# pi_zero_drone_controller_hat.net
KiCad netlist of a schematic drawn in EAGLE
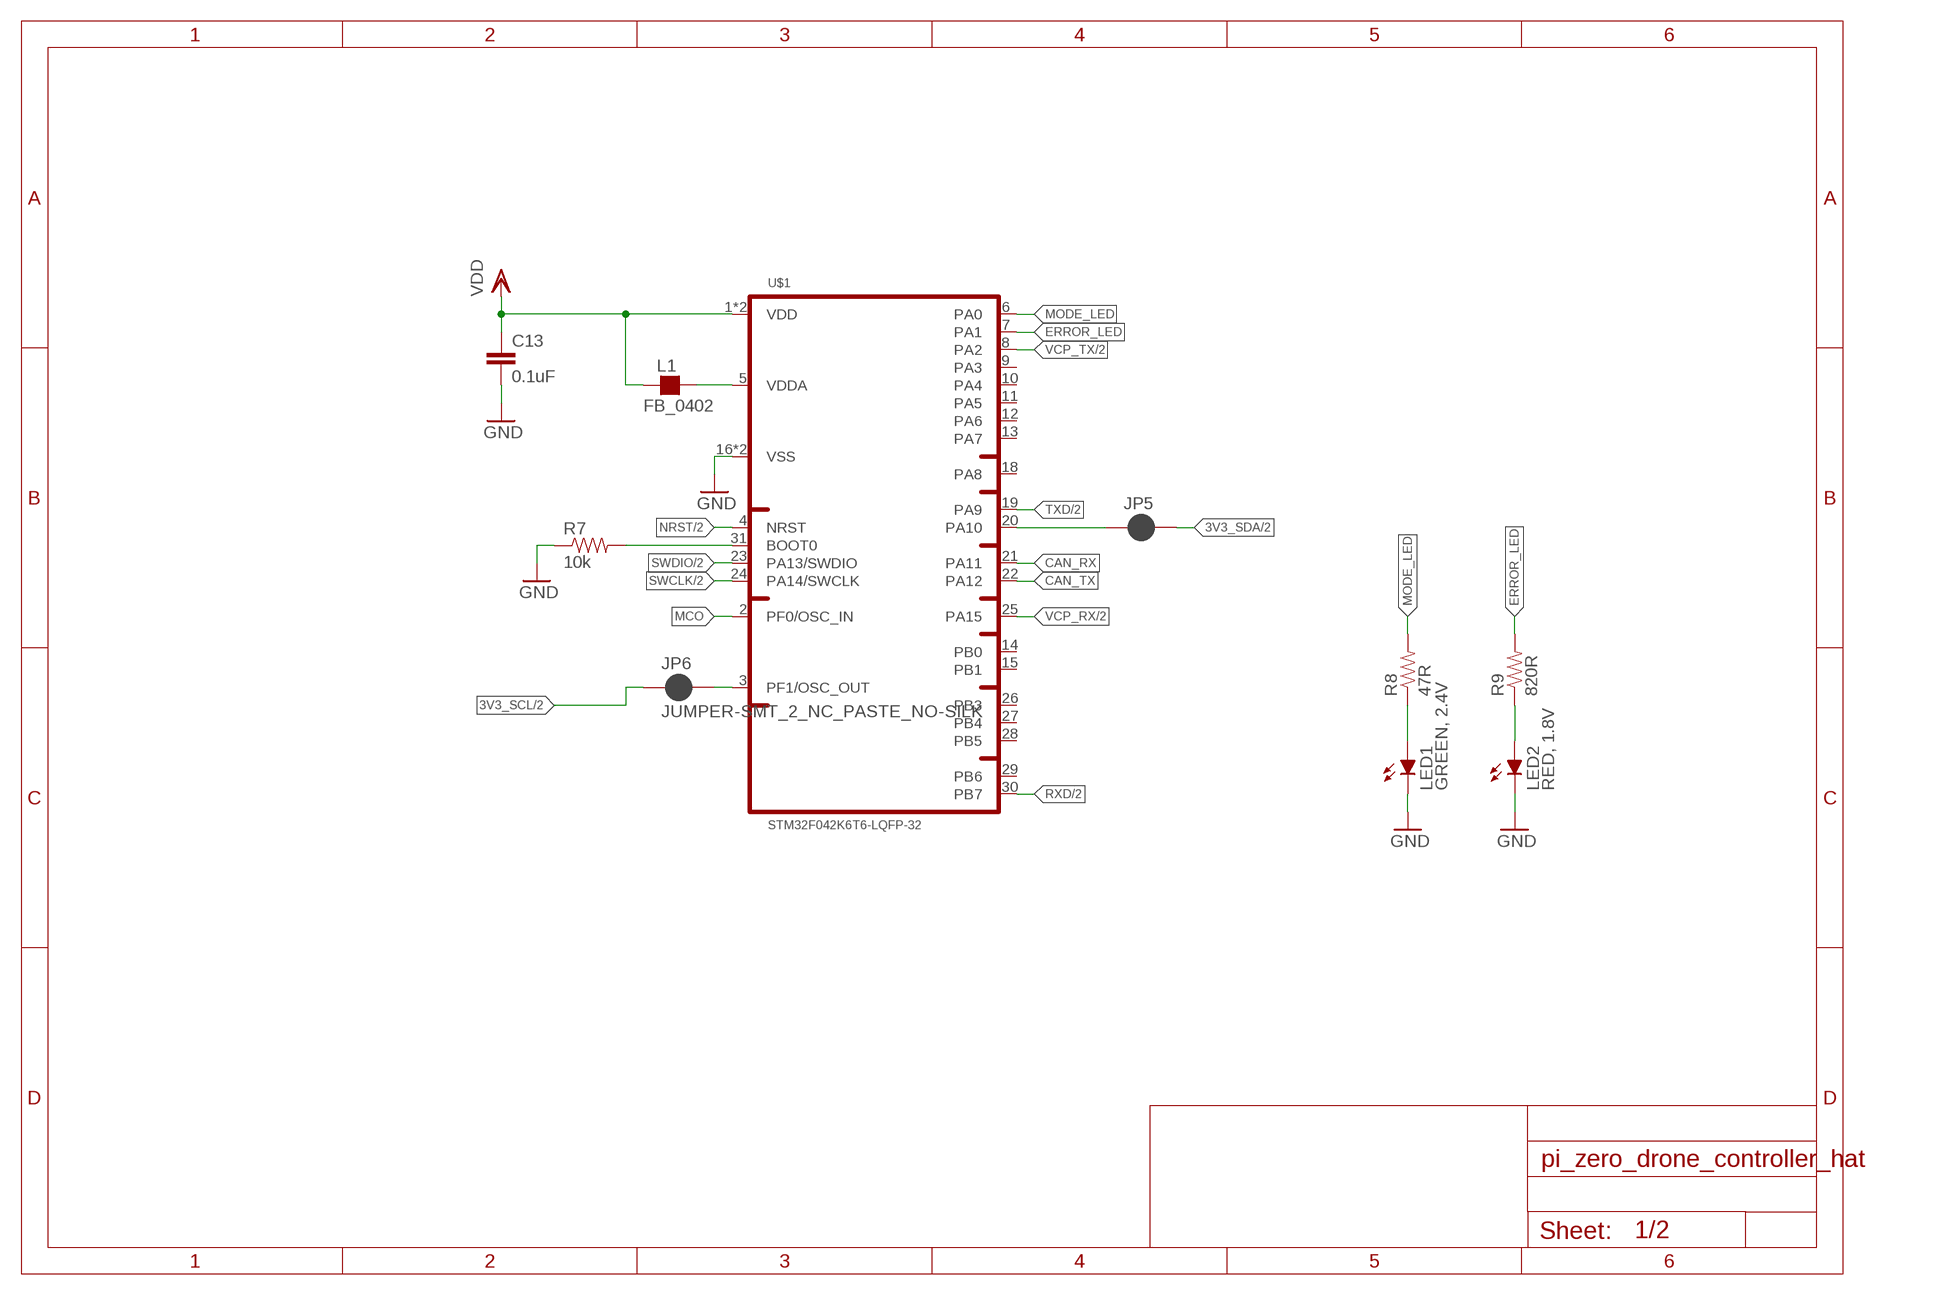
[diagram p0: schematic, sheet 1]
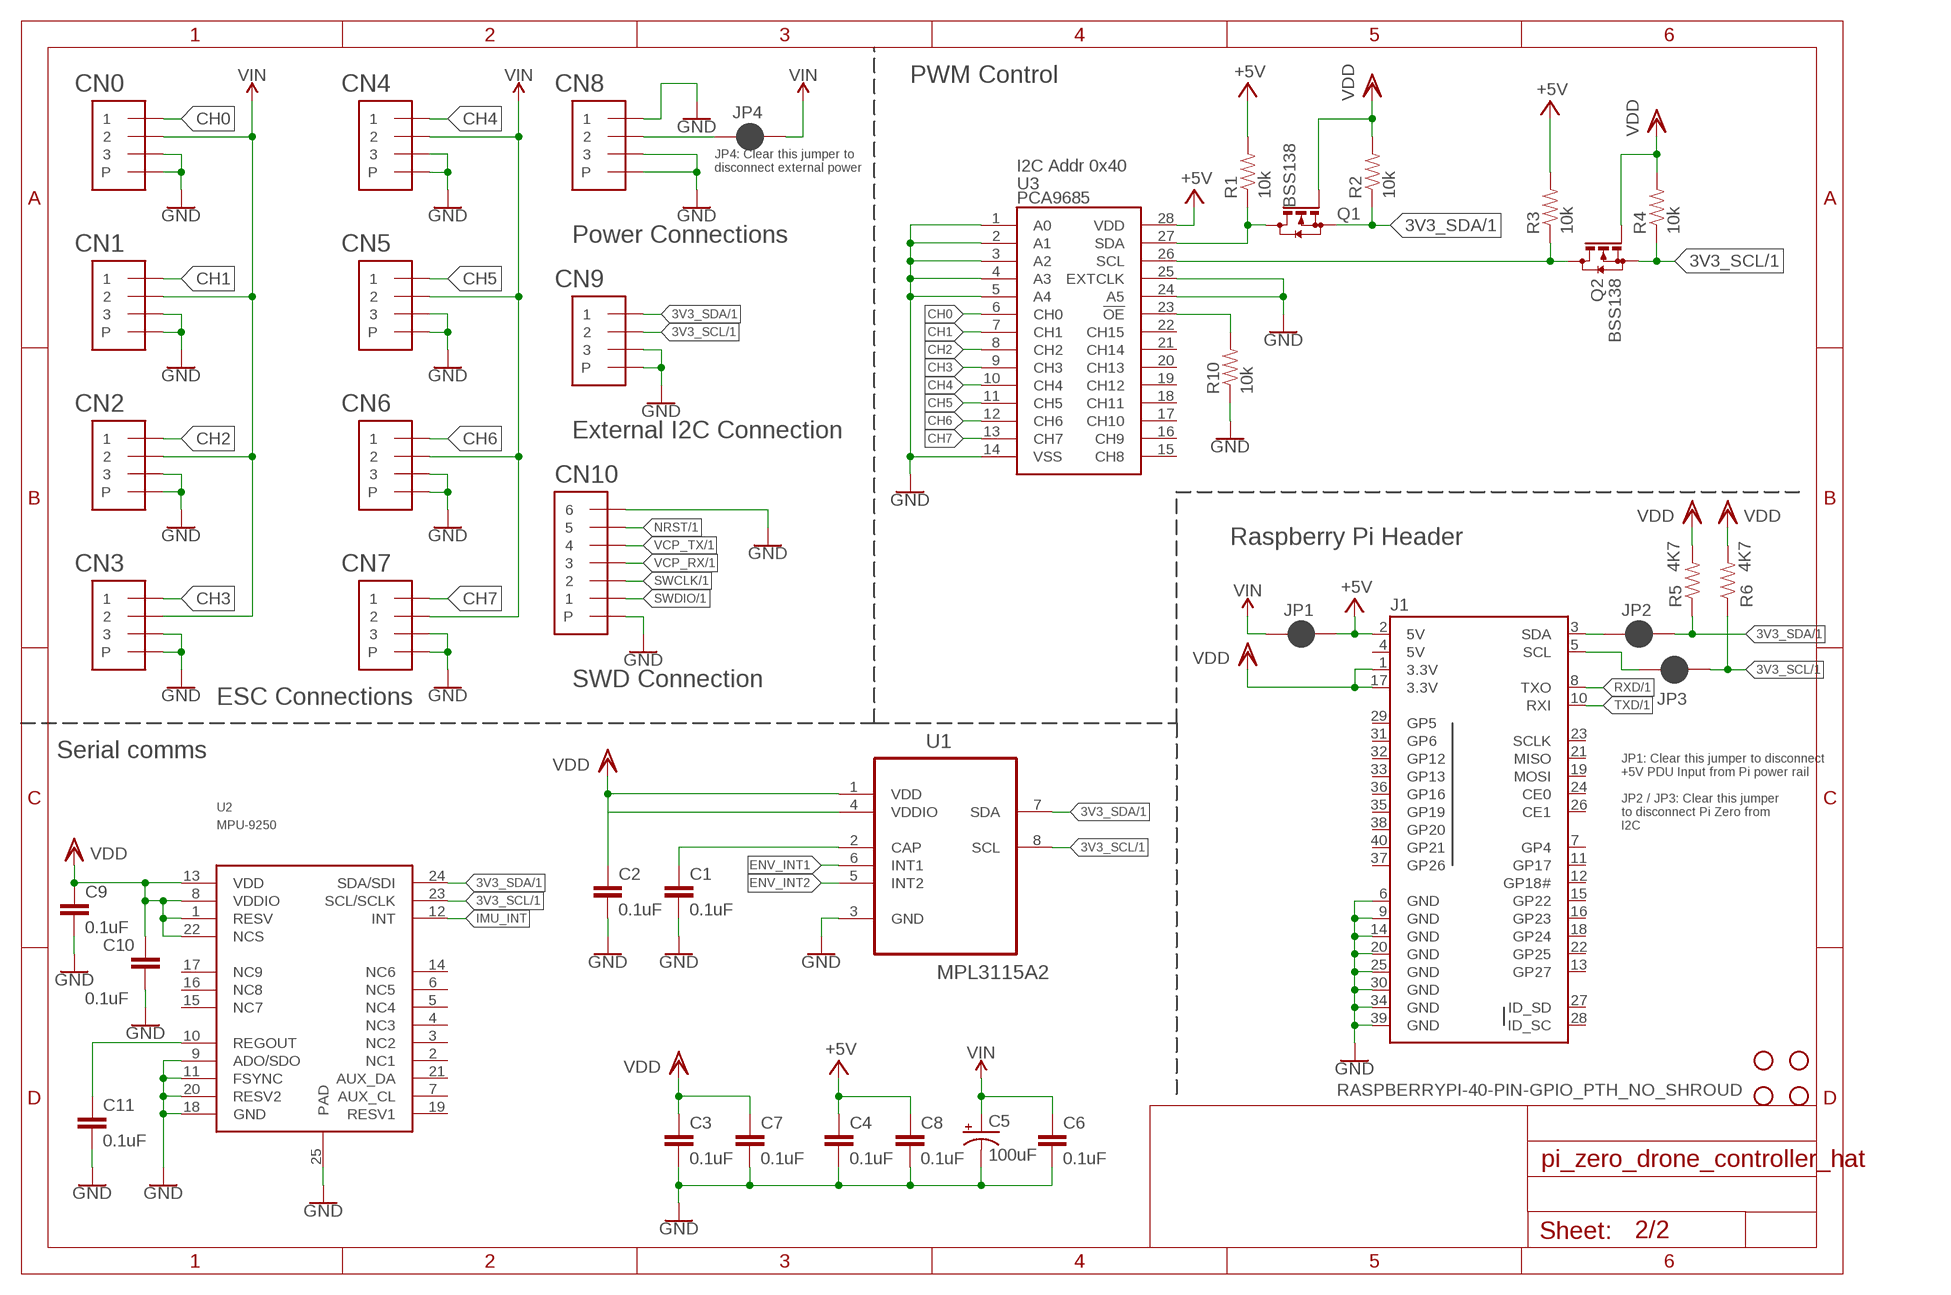
[diagram p1: schematic, sheet 2]

(export (version "E")
  (design (tool "Eeschema 10.0.6"))
  (components
    (comp (ref "C13")
      (value "0.1uF")
      (footprint "eagle-import:0402")
      (libsource (lib "eagle-import") (part "0.1UF-0402-16V-10%"))
    )
    (comp (ref "JP5")
      (value "JUMPER-SMT_2_NC_PASTE_NO-SILK")
      (footprint "eagle-import:SMT-JUMPER_2_NC_PASTE_NO-SILK")
      (libsource (lib "eagle-import") (part "JUMPER-SMT_2_NC_PASTE_NO-SILK"))
    )
    (comp (ref "JP6")
      (value "JUMPER-SMT_2_NC_PASTE_NO-SILK")
      (footprint "eagle-import:SMT-JUMPER_2_NC_PASTE_NO-SILK")
      (libsource (lib "eagle-import") (part "JUMPER-SMT_2_NC_PASTE_NO-SILK"))
    )
    (comp (ref "L1")
      (value "FB_0402")
      (footprint "eagle-import:L0402")
      (libsource (lib "eagle-import") (part "FB_0402"))
    )
    (comp (ref "LED1")
      (value "GREEN, 2.4V")
      (footprint "eagle-import:CHIP-LED0603")
      (libsource (lib "eagle-import") (part "LEDCHIP-LED0603"))
    )
    (comp (ref "LED2")
      (value "RED, 1.8V")
      (footprint "eagle-import:CHIP-LED0603")
      (libsource (lib "eagle-import") (part "LEDCHIP-LED0603"))
    )
    (comp (ref "R7")
      (value "10k")
      (footprint "eagle-import:RES_0402")
      (libsource (lib "eagle-import") (part "SPARKFUN-RESISTORS_RESISTOR"))
    )
    (comp (ref "R8")
      (value "47R")
      (footprint "eagle-import:RES_0402")
      (libsource (lib "eagle-import") (part "SPARKFUN-RESISTORS_RESISTOR"))
    )
    (comp (ref "R9")
      (value "820R")
      (footprint "eagle-import:RES_0402")
      (libsource (lib "eagle-import") (part "SPARKFUN-RESISTORS_RESISTOR"))
    )
    (comp (ref "U$1")
      (value "STM32F042K6T6-LQFP-32")
      (footprint "eagle-import:LQFP-32")
      (libsource (lib "eagle-import") (part "STM32F042K6T6-LQFP-32"))
    )
    (comp (ref "C1")
      (value "0.1uF")
      (footprint "eagle-import:0402")
      (libsource (lib "eagle-import") (part "0.1UF-0402-16V-10%"))
    )
    (comp (ref "C2")
      (value "0.1uF")
      (footprint "eagle-import:0402")
      (libsource (lib "eagle-import") (part "0.1UF-0402-16V-10%"))
    )
    (comp (ref "C3")
      (value "0.1uF")
      (footprint "eagle-import:0402")
      (libsource (lib "eagle-import") (part "0.1UF-0402-16V-10%"))
    )
    (comp (ref "C4")
      (value "0.1uF")
      (footprint "eagle-import:0402")
      (libsource (lib "eagle-import") (part "0.1UF-0402-16V-10%"))
    )
    (comp (ref "C5")
      (value "100uF")
      (footprint "eagle-import:PANASONIC_D")
      (libsource (lib "eagle-import") (part "100UF-POLAR-25V-20%(ELEC)"))
    )
    (comp (ref "C6")
      (value "0.1uF")
      (footprint "eagle-import:0402")
      (libsource (lib "eagle-import") (part "0.1UF-0402-16V-10%"))
    )
    (comp (ref "C7")
      (value "0.1uF")
      (footprint "eagle-import:0402")
      (libsource (lib "eagle-import") (part "0.1UF-0402-16V-10%"))
    )
    (comp (ref "C8")
      (value "0.1uF")
      (footprint "eagle-import:0402")
      (libsource (lib "eagle-import") (part "0.1UF-0402-16V-10%"))
    )
    (comp (ref "C9")
      (value "0.1uF")
      (footprint "eagle-import:0402")
      (libsource (lib "eagle-import") (part "0.1UF-0402-16V-10%"))
    )
    (comp (ref "C10")
      (value "0.1uF")
      (footprint "eagle-import:0402")
      (libsource (lib "eagle-import") (part "0.1UF-0402-16V-10%"))
    )
    (comp (ref "C11")
      (value "0.1uF")
      (footprint "eagle-import:0402")
      (libsource (lib "eagle-import") (part "0.1UF-0402-16V-10%"))
    )
    (comp (ref "CN0")
      (value "JST_SH_3")
      (footprint "eagle-import:JST_SH_3")
      (libsource (lib "eagle-import") (part "JST_SH_3"))
    )
    (comp (ref "CN1")
      (value "JST_SH_3")
      (footprint "eagle-import:JST_SH_3")
      (libsource (lib "eagle-import") (part "JST_SH_3"))
    )
    (comp (ref "CN2")
      (value "JST_SH_3")
      (footprint "eagle-import:JST_SH_3")
      (libsource (lib "eagle-import") (part "JST_SH_3"))
    )
    (comp (ref "CN3")
      (value "JST_SH_3")
      (footprint "eagle-import:JST_SH_3")
      (libsource (lib "eagle-import") (part "JST_SH_3"))
    )
    (comp (ref "CN4")
      (value "JST_SH_3")
      (footprint "eagle-import:JST_SH_3")
      (libsource (lib "eagle-import") (part "JST_SH_3"))
    )
    (comp (ref "CN5")
      (value "JST_SH_3")
      (footprint "eagle-import:JST_SH_3")
      (libsource (lib "eagle-import") (part "JST_SH_3"))
    )
    (comp (ref "CN6")
      (value "JST_SH_3")
      (footprint "eagle-import:JST_SH_3")
      (libsource (lib "eagle-import") (part "JST_SH_3"))
    )
    (comp (ref "CN7")
      (value "JST_SH_3")
      (footprint "eagle-import:JST_SH_3")
      (libsource (lib "eagle-import") (part "JST_SH_3"))
    )
    (comp (ref "CN8")
      (value "JST_SH_3")
      (footprint "eagle-import:JST_SH_3")
      (libsource (lib "eagle-import") (part "JST_SH_3"))
    )
    (comp (ref "CN9")
      (value "JST_SH_3")
      (footprint "eagle-import:JST_SH_3")
      (libsource (lib "eagle-import") (part "JST_SH_3"))
    )
    (comp (ref "CN10")
      (value "JST_SH_6")
      (footprint "eagle-import:JST_SH_6")
      (libsource (lib "eagle-import") (part "JST_SH_6"))
    )
    (comp (ref "H1")
      (value "STAND-OFF")
      (footprint "eagle-import:STAND-OFF")
      (libsource (lib "eagle-import") (part "STAND-OFF"))
    )
    (comp (ref "H2")
      (value "STAND-OFF")
      (footprint "eagle-import:STAND-OFF")
      (libsource (lib "eagle-import") (part "STAND-OFF"))
    )
    (comp (ref "H3")
      (value "STAND-OFF")
      (footprint "eagle-import:STAND-OFF")
      (libsource (lib "eagle-import") (part "STAND-OFF"))
    )
    (comp (ref "H4")
      (value "STAND-OFF")
      (footprint "eagle-import:STAND-OFF")
      (libsource (lib "eagle-import") (part "STAND-OFF"))
    )
    (comp (ref "J1")
      (value "RASPBERRYPI-40-PIN-GPIO_PTH_NO_SHROUD")
      (footprint "eagle-import:2X20")
      (libsource (lib "eagle-import") (part "RASPBERRYPI-40-PIN-GPIO_PTH_NO_SHROUD"))
    )
    (comp (ref "JP1")
      (value "JUMPER-SMT_2_NC_PASTE_NO-SILK")
      (footprint "eagle-import:SMT-JUMPER_2_NC_PASTE_NO-SILK")
      (libsource (lib "eagle-import") (part "JUMPER-SMT_2_NC_PASTE_NO-SILK"))
    )
    (comp (ref "JP2")
      (value "JUMPER-SMT_2_NC_PASTE_NO-SILK")
      (footprint "eagle-import:SMT-JUMPER_2_NC_PASTE_NO-SILK")
      (libsource (lib "eagle-import") (part "JUMPER-SMT_2_NC_PASTE_NO-SILK"))
    )
    (comp (ref "JP3")
      (value "JUMPER-SMT_2_NC_PASTE_NO-SILK")
      (footprint "eagle-import:SMT-JUMPER_2_NC_PASTE_NO-SILK")
      (libsource (lib "eagle-import") (part "JUMPER-SMT_2_NC_PASTE_NO-SILK"))
    )
    (comp (ref "JP4")
      (value "JUMPER-SMT_2_NC_PASTE_NO-SILK")
      (footprint "eagle-import:SMT-JUMPER_2_NC_PASTE_NO-SILK")
      (libsource (lib "eagle-import") (part "JUMPER-SMT_2_NC_PASTE_NO-SILK"))
    )
    (comp (ref "Q1")
      (value "BSS138")
      (footprint "eagle-import:SOT23")
      (libsource (lib "eagle-import") (part "BSS138"))
    )
    (comp (ref "Q2")
      (value "BSS138")
      (footprint "eagle-import:SOT23")
      (libsource (lib "eagle-import") (part "BSS138"))
    )
    (comp (ref "R1")
      (value "10k")
      (footprint "eagle-import:RES_0402")
      (libsource (lib "eagle-import") (part "SPARKFUN-RESISTORS_RESISTOR"))
    )
    (comp (ref "R2")
      (value "10k")
      (footprint "eagle-import:RES_0402")
      (libsource (lib "eagle-import") (part "SPARKFUN-RESISTORS_RESISTOR"))
    )
    (comp (ref "R3")
      (value "10k")
      (footprint "eagle-import:RES_0402")
      (libsource (lib "eagle-import") (part "SPARKFUN-RESISTORS_RESISTOR"))
    )
    (comp (ref "R4")
      (value "10k")
      (footprint "eagle-import:RES_0402")
      (libsource (lib "eagle-import") (part "SPARKFUN-RESISTORS_RESISTOR"))
    )
    (comp (ref "R5")
      (value "4K7")
      (footprint "eagle-import:RES_0402")
      (libsource (lib "eagle-import") (part "SPARKFUN-RESISTORS_RESISTOR"))
    )
    (comp (ref "R6")
      (value "4K7")
      (footprint "eagle-import:RES_0402")
      (libsource (lib "eagle-import") (part "SPARKFUN-RESISTORS_RESISTOR"))
    )
    (comp (ref "R10")
      (value "10k")
      (footprint "eagle-import:RES_0402")
      (libsource (lib "eagle-import") (part "SPARKFUN-RESISTORS_RESISTOR"))
    )
    (comp (ref "U1")
      (value "MPL3115A2")
      (footprint "eagle-import:DFN300X500X120-8N")
      (libsource (lib "eagle-import") (part "MPL3115A2"))
    )
    (comp (ref "U2")
      (value "MPU-9250")
      (footprint "eagle-import:LEAD-QFN24")
      (libsource (lib "eagle-import") (part "MPU-9250"))
    )
    (comp (ref "U3")
      (value "PCA9685")
      (footprint "eagle-import:TSSOP-28_4MM")
      (libsource (lib "eagle-import") (part "PCA9685"))
    )
  )
  (nets
    (net (code "1") (name "+5V") (class "Default")
      (node (ref "C4") (pin "1") (pinfunction "1_1") (pintype "passive"))
      (node (ref "C8") (pin "1") (pinfunction "1_1") (pintype "passive"))
      (node (ref "J1") (pin "2") (pinfunction "5V_2") (pintype "power_in"))
      (node (ref "JP1") (pin "2") (pinfunction "2_2") (pintype "passive"))
      (node (ref "R1") (pin "2") (pinfunction "2_2") (pintype "passive"))
      (node (ref "R3") (pin "2") (pinfunction "2_2") (pintype "passive"))
      (node (ref "U3") (pin "28") (pinfunction "VDD_28") (pintype "bidirectional"))
    )
    (net (code "2") (name "3V3_SCL") (class "Default")
      (node (ref "CN9") (pin "2") (pinfunction "2_2") (pintype "bidirectional"))
      (node (ref "JP3") (pin "2") (pinfunction "2_2") (pintype "passive"))
      (node (ref "JP6") (pin "1") (pinfunction "1_1") (pintype "passive"))
      (node (ref "Q2") (pin "2") (pinfunction "S_2") (pintype "passive"))
      (node (ref "R4") (pin "1") (pinfunction "1_1") (pintype "passive"))
      (node (ref "R6") (pin "1") (pinfunction "1_1") (pintype "passive"))
      (node (ref "U1") (pin "8") (pinfunction "SCL_8") (pintype "input"))
      (node (ref "U2") (pin "23") (pinfunction "SCL/SCLK_23") (pintype "bidirectional"))
    )
    (net (code "3") (name "3V3_SDA") (class "Default")
      (node (ref "CN9") (pin "1") (pinfunction "1_1") (pintype "bidirectional"))
      (node (ref "JP2") (pin "2") (pinfunction "2_2") (pintype "passive"))
      (node (ref "JP5") (pin "2") (pinfunction "2_2") (pintype "passive"))
      (node (ref "Q1") (pin "2") (pinfunction "S_2") (pintype "passive"))
      (node (ref "R2") (pin "1") (pinfunction "1_1") (pintype "passive"))
      (node (ref "R5") (pin "1") (pinfunction "1_1") (pintype "passive"))
      (node (ref "U1") (pin "7") (pinfunction "SDA_7") (pintype "bidirectional"))
      (node (ref "U2") (pin "24") (pinfunction "SDA/SDI_24") (pintype "bidirectional"))
    )
    (net (code "4") (name "5V") (class "Default")
      (node (ref "J1") (pin "4") (pinfunction "5V_4") (pintype "power_in"))
    )
    (net (code "5") (name "CAN_RX") (class "Default")
      (node (ref "U$1") (pin "21") (pinfunction "PA11_21") (pintype "bidirectional"))
    )
    (net (code "6") (name "CAN_TX") (class "Default")
      (node (ref "U$1") (pin "22") (pinfunction "PA12_22") (pintype "bidirectional"))
    )
    (net (code "7") (name "CH0") (class "Default")
      (node (ref "CN0") (pin "1") (pinfunction "1_1") (pintype "bidirectional"))
      (node (ref "U3") (pin "6") (pinfunction "CH0_6") (pintype "bidirectional"))
    )
    (net (code "8") (name "CH1") (class "Default")
      (node (ref "CN1") (pin "1") (pinfunction "1_1") (pintype "bidirectional"))
      (node (ref "U3") (pin "7") (pinfunction "CH1_7") (pintype "bidirectional"))
    )
    (net (code "9") (name "CH2") (class "Default")
      (node (ref "CN2") (pin "1") (pinfunction "1_1") (pintype "bidirectional"))
      (node (ref "U3") (pin "8") (pinfunction "CH2_8") (pintype "bidirectional"))
    )
    (net (code "10") (name "CH3") (class "Default")
      (node (ref "CN3") (pin "1") (pinfunction "1_1") (pintype "bidirectional"))
      (node (ref "U3") (pin "9") (pinfunction "CH3_9") (pintype "bidirectional"))
    )
    (net (code "11") (name "CH4") (class "Default")
      (node (ref "CN4") (pin "1") (pinfunction "1_1") (pintype "bidirectional"))
      (node (ref "U3") (pin "10") (pinfunction "CH4_10") (pintype "bidirectional"))
    )
    (net (code "12") (name "CH5") (class "Default")
      (node (ref "CN5") (pin "1") (pinfunction "1_1") (pintype "bidirectional"))
      (node (ref "U3") (pin "11") (pinfunction "CH5_11") (pintype "bidirectional"))
    )
    (net (code "13") (name "CH6") (class "Default")
      (node (ref "CN6") (pin "1") (pinfunction "1_1") (pintype "bidirectional"))
      (node (ref "U3") (pin "12") (pinfunction "CH6_12") (pintype "bidirectional"))
    )
    (net (code "14") (name "CH7") (class "Default")
      (node (ref "CN7") (pin "1") (pinfunction "1_1") (pintype "bidirectional"))
      (node (ref "U3") (pin "13") (pinfunction "CH7_13") (pintype "bidirectional"))
    )
    (net (code "15") (name "ENV_INT1") (class "Default")
      (node (ref "U1") (pin "6") (pinfunction "INT1_6") (pintype "passive"))
    )
    (net (code "16") (name "ENV_INT2") (class "Default")
      (node (ref "U1") (pin "5") (pinfunction "INT2_5") (pintype "passive"))
    )
    (net (code "17") (name "ERROR_LED") (class "Default")
      (node (ref "R9") (pin "2") (pinfunction "2_2") (pintype "passive"))
      (node (ref "U$1") (pin "7") (pinfunction "PA1_7") (pintype "bidirectional"))
    )
    (net (code "18") (name "GND") (class "Default")
      (node (ref "C1") (pin "2") (pinfunction "2_2") (pintype "passive"))
      (node (ref "C10") (pin "2") (pinfunction "2_2") (pintype "passive"))
      (node (ref "C11") (pin "2") (pinfunction "2_2") (pintype "passive"))
      (node (ref "C13") (pin "2") (pinfunction "2_2") (pintype "passive"))
      (node (ref "C2") (pin "2") (pinfunction "2_2") (pintype "passive"))
      (node (ref "C3") (pin "2") (pinfunction "2_2") (pintype "passive"))
      (node (ref "C4") (pin "2") (pinfunction "2_2") (pintype "passive"))
      (node (ref "C5") (pin "-") (pinfunction "-_-") (pintype "passive"))
      (node (ref "C6") (pin "2") (pinfunction "2_2") (pintype "passive"))
      (node (ref "C7") (pin "2") (pinfunction "2_2") (pintype "passive"))
      (node (ref "C8") (pin "2") (pinfunction "2_2") (pintype "passive"))
      (node (ref "C9") (pin "2") (pinfunction "2_2") (pintype "passive"))
      (node (ref "CN0") (pin "3") (pinfunction "3_3") (pintype "bidirectional"))
      (node (ref "CN0") (pin "P$1") (pinfunction "P_P$1") (pintype "bidirectional"))
      (node (ref "CN0") (pin "P$2") (pinfunction "P_P$2") (pintype "bidirectional"))
      (node (ref "CN1") (pin "3") (pinfunction "3_3") (pintype "bidirectional"))
      (node (ref "CN1") (pin "P$1") (pinfunction "P_P$1") (pintype "bidirectional"))
      (node (ref "CN1") (pin "P$2") (pinfunction "P_P$2") (pintype "bidirectional"))
      (node (ref "CN10") (pin "6") (pinfunction "6_6") (pintype "bidirectional"))
      (node (ref "CN10") (pin "P$1") (pinfunction "P_P$1") (pintype "bidirectional"))
      (node (ref "CN10") (pin "P$2") (pinfunction "P_P$2") (pintype "bidirectional"))
      (node (ref "CN2") (pin "3") (pinfunction "3_3") (pintype "bidirectional"))
      (node (ref "CN2") (pin "P$1") (pinfunction "P_P$1") (pintype "bidirectional"))
      (node (ref "CN2") (pin "P$2") (pinfunction "P_P$2") (pintype "bidirectional"))
      (node (ref "CN3") (pin "3") (pinfunction "3_3") (pintype "bidirectional"))
      (node (ref "CN3") (pin "P$1") (pinfunction "P_P$1") (pintype "bidirectional"))
      (node (ref "CN3") (pin "P$2") (pinfunction "P_P$2") (pintype "bidirectional"))
      (node (ref "CN4") (pin "3") (pinfunction "3_3") (pintype "bidirectional"))
      (node (ref "CN4") (pin "P$1") (pinfunction "P_P$1") (pintype "bidirectional"))
      (node (ref "CN4") (pin "P$2") (pinfunction "P_P$2") (pintype "bidirectional"))
      (node (ref "CN5") (pin "3") (pinfunction "3_3") (pintype "bidirectional"))
      (node (ref "CN5") (pin "P$1") (pinfunction "P_P$1") (pintype "bidirectional"))
      (node (ref "CN5") (pin "P$2") (pinfunction "P_P$2") (pintype "bidirectional"))
      (node (ref "CN6") (pin "3") (pinfunction "3_3") (pintype "bidirectional"))
      (node (ref "CN6") (pin "P$1") (pinfunction "P_P$1") (pintype "bidirectional"))
      (node (ref "CN6") (pin "P$2") (pinfunction "P_P$2") (pintype "bidirectional"))
      (node (ref "CN7") (pin "3") (pinfunction "3_3") (pintype "bidirectional"))
      (node (ref "CN7") (pin "P$1") (pinfunction "P_P$1") (pintype "bidirectional"))
      (node (ref "CN7") (pin "P$2") (pinfunction "P_P$2") (pintype "bidirectional"))
      (node (ref "CN8") (pin "1") (pinfunction "1_1") (pintype "bidirectional"))
      (node (ref "CN8") (pin "3") (pinfunction "3_3") (pintype "bidirectional"))
      (node (ref "CN8") (pin "P$1") (pinfunction "P_P$1") (pintype "bidirectional"))
      (node (ref "CN8") (pin "P$2") (pinfunction "P_P$2") (pintype "bidirectional"))
      (node (ref "CN9") (pin "3") (pinfunction "3_3") (pintype "bidirectional"))
      (node (ref "CN9") (pin "P$1") (pinfunction "P_P$1") (pintype "bidirectional"))
      (node (ref "CN9") (pin "P$2") (pinfunction "P_P$2") (pintype "bidirectional"))
      (node (ref "J1") (pin "14") (pinfunction "GND_14") (pintype "power_in"))
      (node (ref "J1") (pin "20") (pinfunction "GND_20") (pintype "power_in"))
      (node (ref "J1") (pin "25") (pinfunction "GND_25") (pintype "power_in"))
      (node (ref "J1") (pin "30") (pinfunction "GND_30") (pintype "power_in"))
      (node (ref "J1") (pin "34") (pinfunction "GND_34") (pintype "power_in"))
      (node (ref "J1") (pin "39") (pinfunction "GND_39") (pintype "power_in"))
      (node (ref "J1") (pin "6") (pinfunction "GND_6") (pintype "power_in"))
      (node (ref "J1") (pin "9") (pinfunction "GND_9") (pintype "power_in"))
      (node (ref "LED1") (pin "C") (pinfunction "C_C") (pintype "passive"))
      (node (ref "LED2") (pin "C") (pinfunction "C_C") (pintype "passive"))
      (node (ref "R10") (pin "1") (pinfunction "1_1") (pintype "passive"))
      (node (ref "R7") (pin "1") (pinfunction "1_1") (pintype "passive"))
      (node (ref "U$1") (pin "16") (pinfunction "VSS_16") (pintype "bidirectional"))
      (node (ref "U$1") (pin "32") (pinfunction "VSS_32") (pintype "bidirectional"))
      (node (ref "U1") (pin "3") (pinfunction "GND_3") (pintype "power_in"))
      (node (ref "U2") (pin "11") (pinfunction "FSYNC_11") (pintype "bidirectional"))
      (node (ref "U2") (pin "18") (pinfunction "GND_18") (pintype "bidirectional"))
      (node (ref "U2") (pin "20") (pinfunction "RESV2_20") (pintype "bidirectional"))
      (node (ref "U2") (pin "25") (pinfunction "PAD_25") (pintype "bidirectional"))
      (node (ref "U2") (pin "9") (pinfunction "ADO/SDO_9") (pintype "bidirectional"))
      (node (ref "U3") (pin "1") (pinfunction "A0_1") (pintype "bidirectional"))
      (node (ref "U3") (pin "14") (pinfunction "VSS_14") (pintype "bidirectional"))
      (node (ref "U3") (pin "2") (pinfunction "A1_2") (pintype "bidirectional"))
      (node (ref "U3") (pin "24") (pinfunction "A5_24") (pintype "bidirectional"))
      (node (ref "U3") (pin "25") (pinfunction "EXTCLK_25") (pintype "bidirectional"))
      (node (ref "U3") (pin "3") (pinfunction "A2_3") (pintype "bidirectional"))
      (node (ref "U3") (pin "4") (pinfunction "A3_4") (pintype "bidirectional"))
      (node (ref "U3") (pin "5") (pinfunction "A4_5") (pintype "bidirectional"))
    )
    (net (code "19") (name "IMU_INT") (class "Default")
      (node (ref "U2") (pin "12") (pinfunction "INT_12") (pintype "bidirectional"))
    )
    (net (code "20") (name "MCO") (class "Default")
      (node (ref "U$1") (pin "2") (pinfunction "PF0/OSC_IN_2") (pintype "bidirectional"))
    )
    (net (code "21") (name "MODE_LED") (class "Default")
      (node (ref "R8") (pin "2") (pinfunction "2_2") (pintype "passive"))
      (node (ref "U$1") (pin "6") (pinfunction "PA0_6") (pintype "bidirectional"))
    )
    (net (code "22") (name "NRST") (class "Default")
      (node (ref "CN10") (pin "5") (pinfunction "5_5") (pintype "bidirectional"))
      (node (ref "U$1") (pin "4") (pinfunction "NRST_4") (pintype "bidirectional"))
    )
    (net (code "23") (name "Net-(CN8-Pad2)") (class "Default")
      (node (ref "CN8") (pin "2") (pinfunction "2_2") (pintype "bidirectional"))
      (node (ref "JP4") (pin "1") (pinfunction "1_1") (pintype "passive"))
    )
    (net (code "24") (name "Net-(J1-SCL)") (class "Default")
      (node (ref "J1") (pin "5") (pinfunction "SCL_5") (pintype "bidirectional"))
      (node (ref "JP3") (pin "1") (pinfunction "1_1") (pintype "passive"))
    )
    (net (code "25") (name "Net-(J1-SDA)") (class "Default")
      (node (ref "J1") (pin "3") (pinfunction "SDA_3") (pintype "bidirectional"))
      (node (ref "JP2") (pin "1") (pinfunction "1_1") (pintype "passive"))
    )
    (net (code "26") (name "Net-(LED1-PadA)") (class "Default")
      (node (ref "LED1") (pin "A") (pinfunction "A_A") (pintype "passive"))
      (node (ref "R8") (pin "1") (pinfunction "1_1") (pintype "passive"))
    )
    (net (code "27") (name "Net-(LED2-PadA)") (class "Default")
      (node (ref "LED2") (pin "A") (pinfunction "A_A") (pintype "passive"))
      (node (ref "R9") (pin "1") (pinfunction "1_1") (pintype "passive"))
    )
    (net (code "28") (name "Net-(Q1-D)") (class "Default")
      (node (ref "Q1") (pin "3") (pinfunction "D_3") (pintype "passive"))
      (node (ref "R1") (pin "1") (pinfunction "1_1") (pintype "passive"))
      (node (ref "U3") (pin "27") (pinfunction "SDA_27") (pintype "bidirectional"))
    )
    (net (code "29") (name "Net-(Q2-D)") (class "Default")
      (node (ref "Q2") (pin "3") (pinfunction "D_3") (pintype "passive"))
      (node (ref "R3") (pin "1") (pinfunction "1_1") (pintype "passive"))
      (node (ref "U3") (pin "26") (pinfunction "SCL_26") (pintype "bidirectional"))
    )
    (net (code "30") (name "Net-(U$1-BOOT0)") (class "Default")
      (node (ref "R7") (pin "2") (pinfunction "2_2") (pintype "passive"))
      (node (ref "U$1") (pin "31") (pinfunction "BOOT0_31") (pintype "bidirectional"))
    )
    (net (code "31") (name "Net-(U$1-PA10)") (class "Default")
      (node (ref "JP5") (pin "1") (pinfunction "1_1") (pintype "passive"))
      (node (ref "U$1") (pin "20") (pinfunction "PA10_20") (pintype "bidirectional"))
    )
    (net (code "32") (name "Net-(U$1-PF1{slash}OSC_OUT)") (class "Default")
      (node (ref "JP6") (pin "2") (pinfunction "2_2") (pintype "passive"))
      (node (ref "U$1") (pin "3") (pinfunction "PF1/OSC_OUT_3") (pintype "bidirectional"))
    )
    (net (code "33") (name "Net-(U$1-VDDA)") (class "Default")
      (node (ref "L1") (pin "2") (pinfunction "2_2") (pintype "passive"))
      (node (ref "U$1") (pin "5") (pinfunction "VDDA_5") (pintype "bidirectional"))
    )
    (net (code "34") (name "Net-(U1-CAP)") (class "Default")
      (node (ref "C1") (pin "1") (pinfunction "1_1") (pintype "passive"))
      (node (ref "U1") (pin "2") (pinfunction "CAP_2") (pintype "passive"))
    )
    (net (code "35") (name "Net-(U2-REGOUT)") (class "Default")
      (node (ref "C11") (pin "1") (pinfunction "1_1") (pintype "passive"))
      (node (ref "U2") (pin "10") (pinfunction "REGOUT_10") (pintype "bidirectional"))
    )
    (net (code "36") (name "Net-(U3-~{OE})") (class "Default")
      (node (ref "R10") (pin "2") (pinfunction "2_2") (pintype "passive"))
      (node (ref "U3") (pin "23") (pinfunction "~{OE}_23") (pintype "bidirectional"))
    )
    (net (code "37") (name "RXD") (class "Default")
      (node (ref "J1") (pin "8") (pinfunction "TXO_8") (pintype "output"))
      (node (ref "U$1") (pin "30") (pinfunction "PB7_30") (pintype "bidirectional"))
    )
    (net (code "38") (name "SWCLK") (class "Default")
      (node (ref "CN10") (pin "2") (pinfunction "2_2") (pintype "bidirectional"))
      (node (ref "U$1") (pin "24") (pinfunction "PA14/SWCLK_24") (pintype "bidirectional"))
    )
    (net (code "39") (name "SWDIO") (class "Default")
      (node (ref "CN10") (pin "1") (pinfunction "1_1") (pintype "bidirectional"))
      (node (ref "U$1") (pin "23") (pinfunction "PA13/SWDIO_23") (pintype "bidirectional"))
    )
    (net (code "40") (name "TXD") (class "Default")
      (node (ref "J1") (pin "10") (pinfunction "RXI_10") (pintype "input"))
      (node (ref "U$1") (pin "19") (pinfunction "PA9_19") (pintype "bidirectional"))
    )
    (net (code "41") (name "VCP_RX") (class "Default")
      (node (ref "CN10") (pin "3") (pinfunction "3_3") (pintype "bidirectional"))
      (node (ref "U$1") (pin "25") (pinfunction "PA15_25") (pintype "bidirectional"))
    )
    (net (code "42") (name "VCP_TX") (class "Default")
      (node (ref "CN10") (pin "4") (pinfunction "4_4") (pintype "bidirectional"))
      (node (ref "U$1") (pin "8") (pinfunction "PA2_8") (pintype "bidirectional"))
    )
    (net (code "43") (name "VDD") (class "Default")
      (node (ref "C10") (pin "1") (pinfunction "1_1") (pintype "passive"))
      (node (ref "C13") (pin "1") (pinfunction "1_1") (pintype "passive"))
      (node (ref "C2") (pin "1") (pinfunction "1_1") (pintype "passive"))
      (node (ref "C3") (pin "1") (pinfunction "1_1") (pintype "passive"))
      (node (ref "C7") (pin "1") (pinfunction "1_1") (pintype "passive"))
      (node (ref "C9") (pin "1") (pinfunction "1_1") (pintype "passive"))
      (node (ref "J1") (pin "1") (pinfunction "3.3V_1") (pintype "power_in"))
      (node (ref "J1") (pin "17") (pinfunction "3.3V_17") (pintype "power_in"))
      (node (ref "L1") (pin "1") (pinfunction "1_1") (pintype "passive"))
      (node (ref "Q1") (pin "1") (pinfunction "G_1") (pintype "passive"))
      (node (ref "Q2") (pin "1") (pinfunction "G_1") (pintype "passive"))
      (node (ref "R2") (pin "2") (pinfunction "2_2") (pintype "passive"))
      (node (ref "R4") (pin "2") (pinfunction "2_2") (pintype "passive"))
      (node (ref "R5") (pin "2") (pinfunction "2_2") (pintype "passive"))
      (node (ref "R6") (pin "2") (pinfunction "2_2") (pintype "passive"))
      (node (ref "U$1") (pin "1") (pinfunction "VDD_1") (pintype "bidirectional"))
      (node (ref "U$1") (pin "17") (pinfunction "VDD_17") (pintype "bidirectional"))
      (node (ref "U1") (pin "1") (pinfunction "VDD_1") (pintype "power_in"))
      (node (ref "U1") (pin "4") (pinfunction "VDDIO_4") (pintype "power_in"))
      (node (ref "U2") (pin "1") (pinfunction "RESV_1") (pintype "bidirectional"))
      (node (ref "U2") (pin "13") (pinfunction "VDD_13") (pintype "bidirectional"))
      (node (ref "U2") (pin "22") (pinfunction "NCS_22") (pintype "bidirectional"))
      (node (ref "U2") (pin "8") (pinfunction "VDDIO_8") (pintype "bidirectional"))
    )
    (net (code "44") (name "VIN") (class "Default")
      (node (ref "C5") (pin "+") (pinfunction "+_+") (pintype "passive"))
      (node (ref "C6") (pin "1") (pinfunction "1_1") (pintype "passive"))
      (node (ref "CN0") (pin "2") (pinfunction "2_2") (pintype "bidirectional"))
      (node (ref "CN1") (pin "2") (pinfunction "2_2") (pintype "bidirectional"))
      (node (ref "CN2") (pin "2") (pinfunction "2_2") (pintype "bidirectional"))
      (node (ref "CN3") (pin "2") (pinfunction "2_2") (pintype "bidirectional"))
      (node (ref "CN4") (pin "2") (pinfunction "2_2") (pintype "bidirectional"))
      (node (ref "CN5") (pin "2") (pinfunction "2_2") (pintype "bidirectional"))
      (node (ref "CN6") (pin "2") (pinfunction "2_2") (pintype "bidirectional"))
      (node (ref "CN7") (pin "2") (pinfunction "2_2") (pintype "bidirectional"))
      (node (ref "JP1") (pin "1") (pinfunction "1_1") (pintype "passive"))
      (node (ref "JP4") (pin "2") (pinfunction "2_2") (pintype "passive"))
    )
    (net (code "45") (name "unconnected-(J1-CE0-Pad24)") (class "Default")
      (node (ref "J1") (pin "24") (pinfunction "CE0_24") (pintype "output"))
    )
    (net (code "46") (name "unconnected-(J1-CE1-Pad26)") (class "Default")
      (node (ref "J1") (pin "26") (pinfunction "CE1_26") (pintype "output"))
    )
    (net (code "47") (name "unconnected-(J1-GP4-Pad7)") (class "Default")
      (node (ref "J1") (pin "7") (pinfunction "GP4_7") (pintype "bidirectional"))
    )
    (net (code "48") (name "unconnected-(J1-GP5-Pad29)") (class "Default")
      (node (ref "J1") (pin "29") (pinfunction "GP5_29") (pintype "bidirectional"))
    )
    (net (code "49") (name "unconnected-(J1-GP6-Pad31)") (class "Default")
      (node (ref "J1") (pin "31") (pinfunction "GP6_31") (pintype "bidirectional"))
    )
    (net (code "50") (name "unconnected-(J1-GP12-Pad32)") (class "Default")
      (node (ref "J1") (pin "32") (pinfunction "GP12_32") (pintype "bidirectional"))
    )
    (net (code "51") (name "unconnected-(J1-GP13-Pad33)") (class "Default")
      (node (ref "J1") (pin "33") (pinfunction "GP13_33") (pintype "bidirectional"))
    )
    (net (code "52") (name "unconnected-(J1-GP16-Pad36)") (class "Default")
      (node (ref "J1") (pin "36") (pinfunction "GP16_36") (pintype "bidirectional"))
    )
    (net (code "53") (name "unconnected-(J1-GP17-Pad11)") (class "Default")
      (node (ref "J1") (pin "11") (pinfunction "GP17_11") (pintype "bidirectional"))
    )
    (net (code "54") (name "unconnected-(J1-GP18#-Pad12)") (class "Default")
      (node (ref "J1") (pin "12") (pinfunction "GP18#_12") (pintype "bidirectional"))
    )
    (net (code "55") (name "unconnected-(J1-GP19-Pad35)") (class "Default")
      (node (ref "J1") (pin "35") (pinfunction "GP19_35") (pintype "bidirectional"))
    )
    (net (code "56") (name "unconnected-(J1-GP20-Pad38)") (class "Default")
      (node (ref "J1") (pin "38") (pinfunction "GP20_38") (pintype "bidirectional"))
    )
    (net (code "57") (name "unconnected-(J1-GP21-Pad40)") (class "Default")
      (node (ref "J1") (pin "40") (pinfunction "GP21_40") (pintype "bidirectional"))
    )
    (net (code "58") (name "unconnected-(J1-GP22-Pad15)") (class "Default")
      (node (ref "J1") (pin "15") (pinfunction "GP22_15") (pintype "bidirectional"))
    )
    (net (code "59") (name "unconnected-(J1-GP23-Pad16)") (class "Default")
      (node (ref "J1") (pin "16") (pinfunction "GP23_16") (pintype "bidirectional"))
    )
    (net (code "60") (name "unconnected-(J1-GP24-Pad18)") (class "Default")
      (node (ref "J1") (pin "18") (pinfunction "GP24_18") (pintype "bidirectional"))
    )
    (net (code "61") (name "unconnected-(J1-GP25-Pad22)") (class "Default")
      (node (ref "J1") (pin "22") (pinfunction "GP25_22") (pintype "bidirectional"))
    )
    (net (code "62") (name "unconnected-(J1-GP26-Pad37)") (class "Default")
      (node (ref "J1") (pin "37") (pinfunction "GP26_37") (pintype "bidirectional"))
    )
    (net (code "63") (name "unconnected-(J1-GP27-Pad13)") (class "Default")
      (node (ref "J1") (pin "13") (pinfunction "GP27_13") (pintype "bidirectional"))
    )
    (net (code "64") (name "unconnected-(J1-ID_SC-Pad28)") (class "Default")
      (node (ref "J1") (pin "28") (pinfunction "ID_SC_28") (pintype "bidirectional"))
    )
    (net (code "65") (name "unconnected-(J1-ID_SD-Pad27)") (class "Default")
      (node (ref "J1") (pin "27") (pinfunction "ID_SD_27") (pintype "bidirectional"))
    )
    (net (code "66") (name "unconnected-(J1-MISO-Pad21)") (class "Default")
      (node (ref "J1") (pin "21") (pinfunction "MISO_21") (pintype "input"))
    )
    (net (code "67") (name "unconnected-(J1-MOSI-Pad19)") (class "Default")
      (node (ref "J1") (pin "19") (pinfunction "MOSI_19") (pintype "output"))
    )
    (net (code "68") (name "unconnected-(J1-SCLK-Pad23)") (class "Default")
      (node (ref "J1") (pin "23") (pinfunction "SCLK_23") (pintype "output"))
    )
    (net (code "69") (name "unconnected-(U$1-PA3-Pad9)") (class "Default")
      (node (ref "U$1") (pin "9") (pinfunction "PA3_9") (pintype "bidirectional"))
    )
    (net (code "70") (name "unconnected-(U$1-PA4-Pad10)") (class "Default")
      (node (ref "U$1") (pin "10") (pinfunction "PA4_10") (pintype "bidirectional"))
    )
    (net (code "71") (name "unconnected-(U$1-PA5-Pad11)") (class "Default")
      (node (ref "U$1") (pin "11") (pinfunction "PA5_11") (pintype "bidirectional"))
    )
    (net (code "72") (name "unconnected-(U$1-PA6-Pad12)") (class "Default")
      (node (ref "U$1") (pin "12") (pinfunction "PA6_12") (pintype "bidirectional"))
    )
    (net (code "73") (name "unconnected-(U$1-PA7-Pad13)") (class "Default")
      (node (ref "U$1") (pin "13") (pinfunction "PA7_13") (pintype "bidirectional"))
    )
    (net (code "74") (name "unconnected-(U$1-PA8-Pad18)") (class "Default")
      (node (ref "U$1") (pin "18") (pinfunction "PA8_18") (pintype "bidirectional"))
    )
    (net (code "75") (name "unconnected-(U$1-PB0-Pad14)") (class "Default")
      (node (ref "U$1") (pin "14") (pinfunction "PB0_14") (pintype "bidirectional"))
    )
    (net (code "76") (name "unconnected-(U$1-PB1-Pad15)") (class "Default")
      (node (ref "U$1") (pin "15") (pinfunction "PB1_15") (pintype "bidirectional"))
    )
    (net (code "77") (name "unconnected-(U$1-PB3-Pad26)") (class "Default")
      (node (ref "U$1") (pin "26") (pinfunction "PB3_26") (pintype "bidirectional"))
    )
    (net (code "78") (name "unconnected-(U$1-PB4-Pad27)") (class "Default")
      (node (ref "U$1") (pin "27") (pinfunction "PB4_27") (pintype "bidirectional"))
    )
    (net (code "79") (name "unconnected-(U$1-PB5-Pad28)") (class "Default")
      (node (ref "U$1") (pin "28") (pinfunction "PB5_28") (pintype "bidirectional"))
    )
    (net (code "80") (name "unconnected-(U$1-PB6-Pad29)") (class "Default")
      (node (ref "U$1") (pin "29") (pinfunction "PB6_29") (pintype "bidirectional"))
    )
    (net (code "81") (name "unconnected-(U2-AUX_CL-Pad7)") (class "Default")
      (node (ref "U2") (pin "7") (pinfunction "AUX_CL_7") (pintype "bidirectional"))
    )
    (net (code "82") (name "unconnected-(U2-AUX_DA-Pad21)") (class "Default")
      (node (ref "U2") (pin "21") (pinfunction "AUX_DA_21") (pintype "bidirectional"))
    )
    (net (code "83") (name "unconnected-(U2-NC1-Pad2)") (class "Default")
      (node (ref "U2") (pin "2") (pinfunction "NC1_2") (pintype "bidirectional"))
    )
    (net (code "84") (name "unconnected-(U2-NC2-Pad3)") (class "Default")
      (node (ref "U2") (pin "3") (pinfunction "NC2_3") (pintype "bidirectional"))
    )
    (net (code "85") (name "unconnected-(U2-NC3-Pad4)") (class "Default")
      (node (ref "U2") (pin "4") (pinfunction "NC3_4") (pintype "bidirectional"))
    )
    (net (code "86") (name "unconnected-(U2-NC4-Pad5)") (class "Default")
      (node (ref "U2") (pin "5") (pinfunction "NC4_5") (pintype "bidirectional"))
    )
    (net (code "87") (name "unconnected-(U2-NC5-Pad6)") (class "Default")
      (node (ref "U2") (pin "6") (pinfunction "NC5_6") (pintype "bidirectional"))
    )
    (net (code "88") (name "unconnected-(U2-NC6-Pad14)") (class "Default")
      (node (ref "U2") (pin "14") (pinfunction "NC6_14") (pintype "bidirectional"))
    )
    (net (code "89") (name "unconnected-(U2-NC7-Pad15)") (class "Default")
      (node (ref "U2") (pin "15") (pinfunction "NC7_15") (pintype "bidirectional"))
    )
    (net (code "90") (name "unconnected-(U2-NC8-Pad16)") (class "Default")
      (node (ref "U2") (pin "16") (pinfunction "NC8_16") (pintype "bidirectional"))
    )
    (net (code "91") (name "unconnected-(U2-NC9-Pad17)") (class "Default")
      (node (ref "U2") (pin "17") (pinfunction "NC9_17") (pintype "no_connect"))
    )
    (net (code "92") (name "unconnected-(U2-RESV1-Pad19)") (class "Default")
      (node (ref "U2") (pin "19") (pinfunction "RESV1_19") (pintype "bidirectional"))
    )
    (net (code "93") (name "unconnected-(U3-CH8-Pad15)") (class "Default")
      (node (ref "U3") (pin "15") (pinfunction "CH8_15") (pintype "bidirectional"))
    )
    (net (code "94") (name "unconnected-(U3-CH9-Pad16)") (class "Default")
      (node (ref "U3") (pin "16") (pinfunction "CH9_16") (pintype "bidirectional"))
    )
    (net (code "95") (name "unconnected-(U3-CH10-Pad17)") (class "Default")
      (node (ref "U3") (pin "17") (pinfunction "CH10_17") (pintype "bidirectional"))
    )
    (net (code "96") (name "unconnected-(U3-CH11-Pad18)") (class "Default")
      (node (ref "U3") (pin "18") (pinfunction "CH11_18") (pintype "bidirectional"))
    )
    (net (code "97") (name "unconnected-(U3-CH12-Pad19)") (class "Default")
      (node (ref "U3") (pin "19") (pinfunction "CH12_19") (pintype "bidirectional"))
    )
    (net (code "98") (name "unconnected-(U3-CH13-Pad20)") (class "Default")
      (node (ref "U3") (pin "20") (pinfunction "CH13_20") (pintype "bidirectional"))
    )
    (net (code "99") (name "unconnected-(U3-CH14-Pad21)") (class "Default")
      (node (ref "U3") (pin "21") (pinfunction "CH14_21") (pintype "bidirectional"))
    )
    (net (code "100") (name "unconnected-(U3-CH15-Pad22)") (class "Default")
      (node (ref "U3") (pin "22") (pinfunction "CH15_22") (pintype "bidirectional"))
    )
  )
)
